# 2020-08-18_Motor_Board.net
KiCad netlist of a schematic drawn in EAGLE
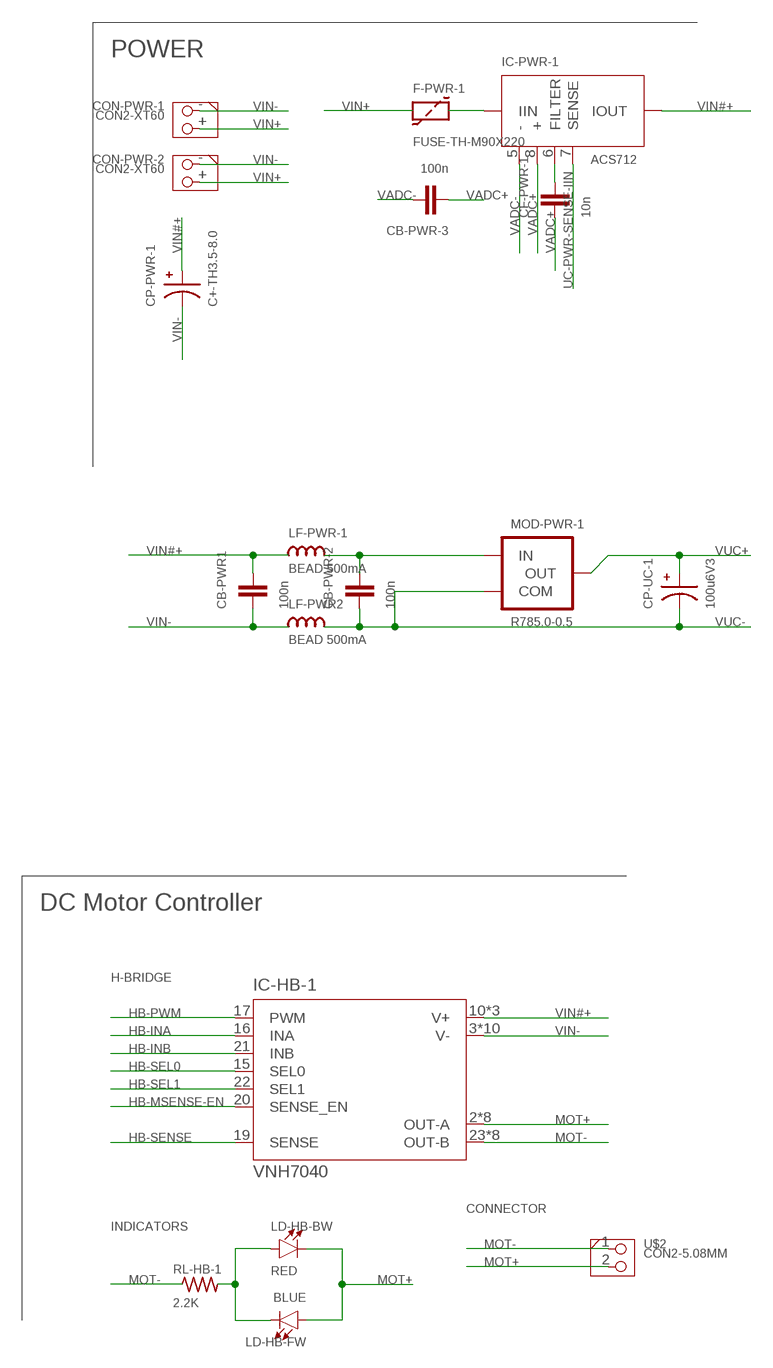
[diagram p0: schematic, sheet 1, part 1 of 2]
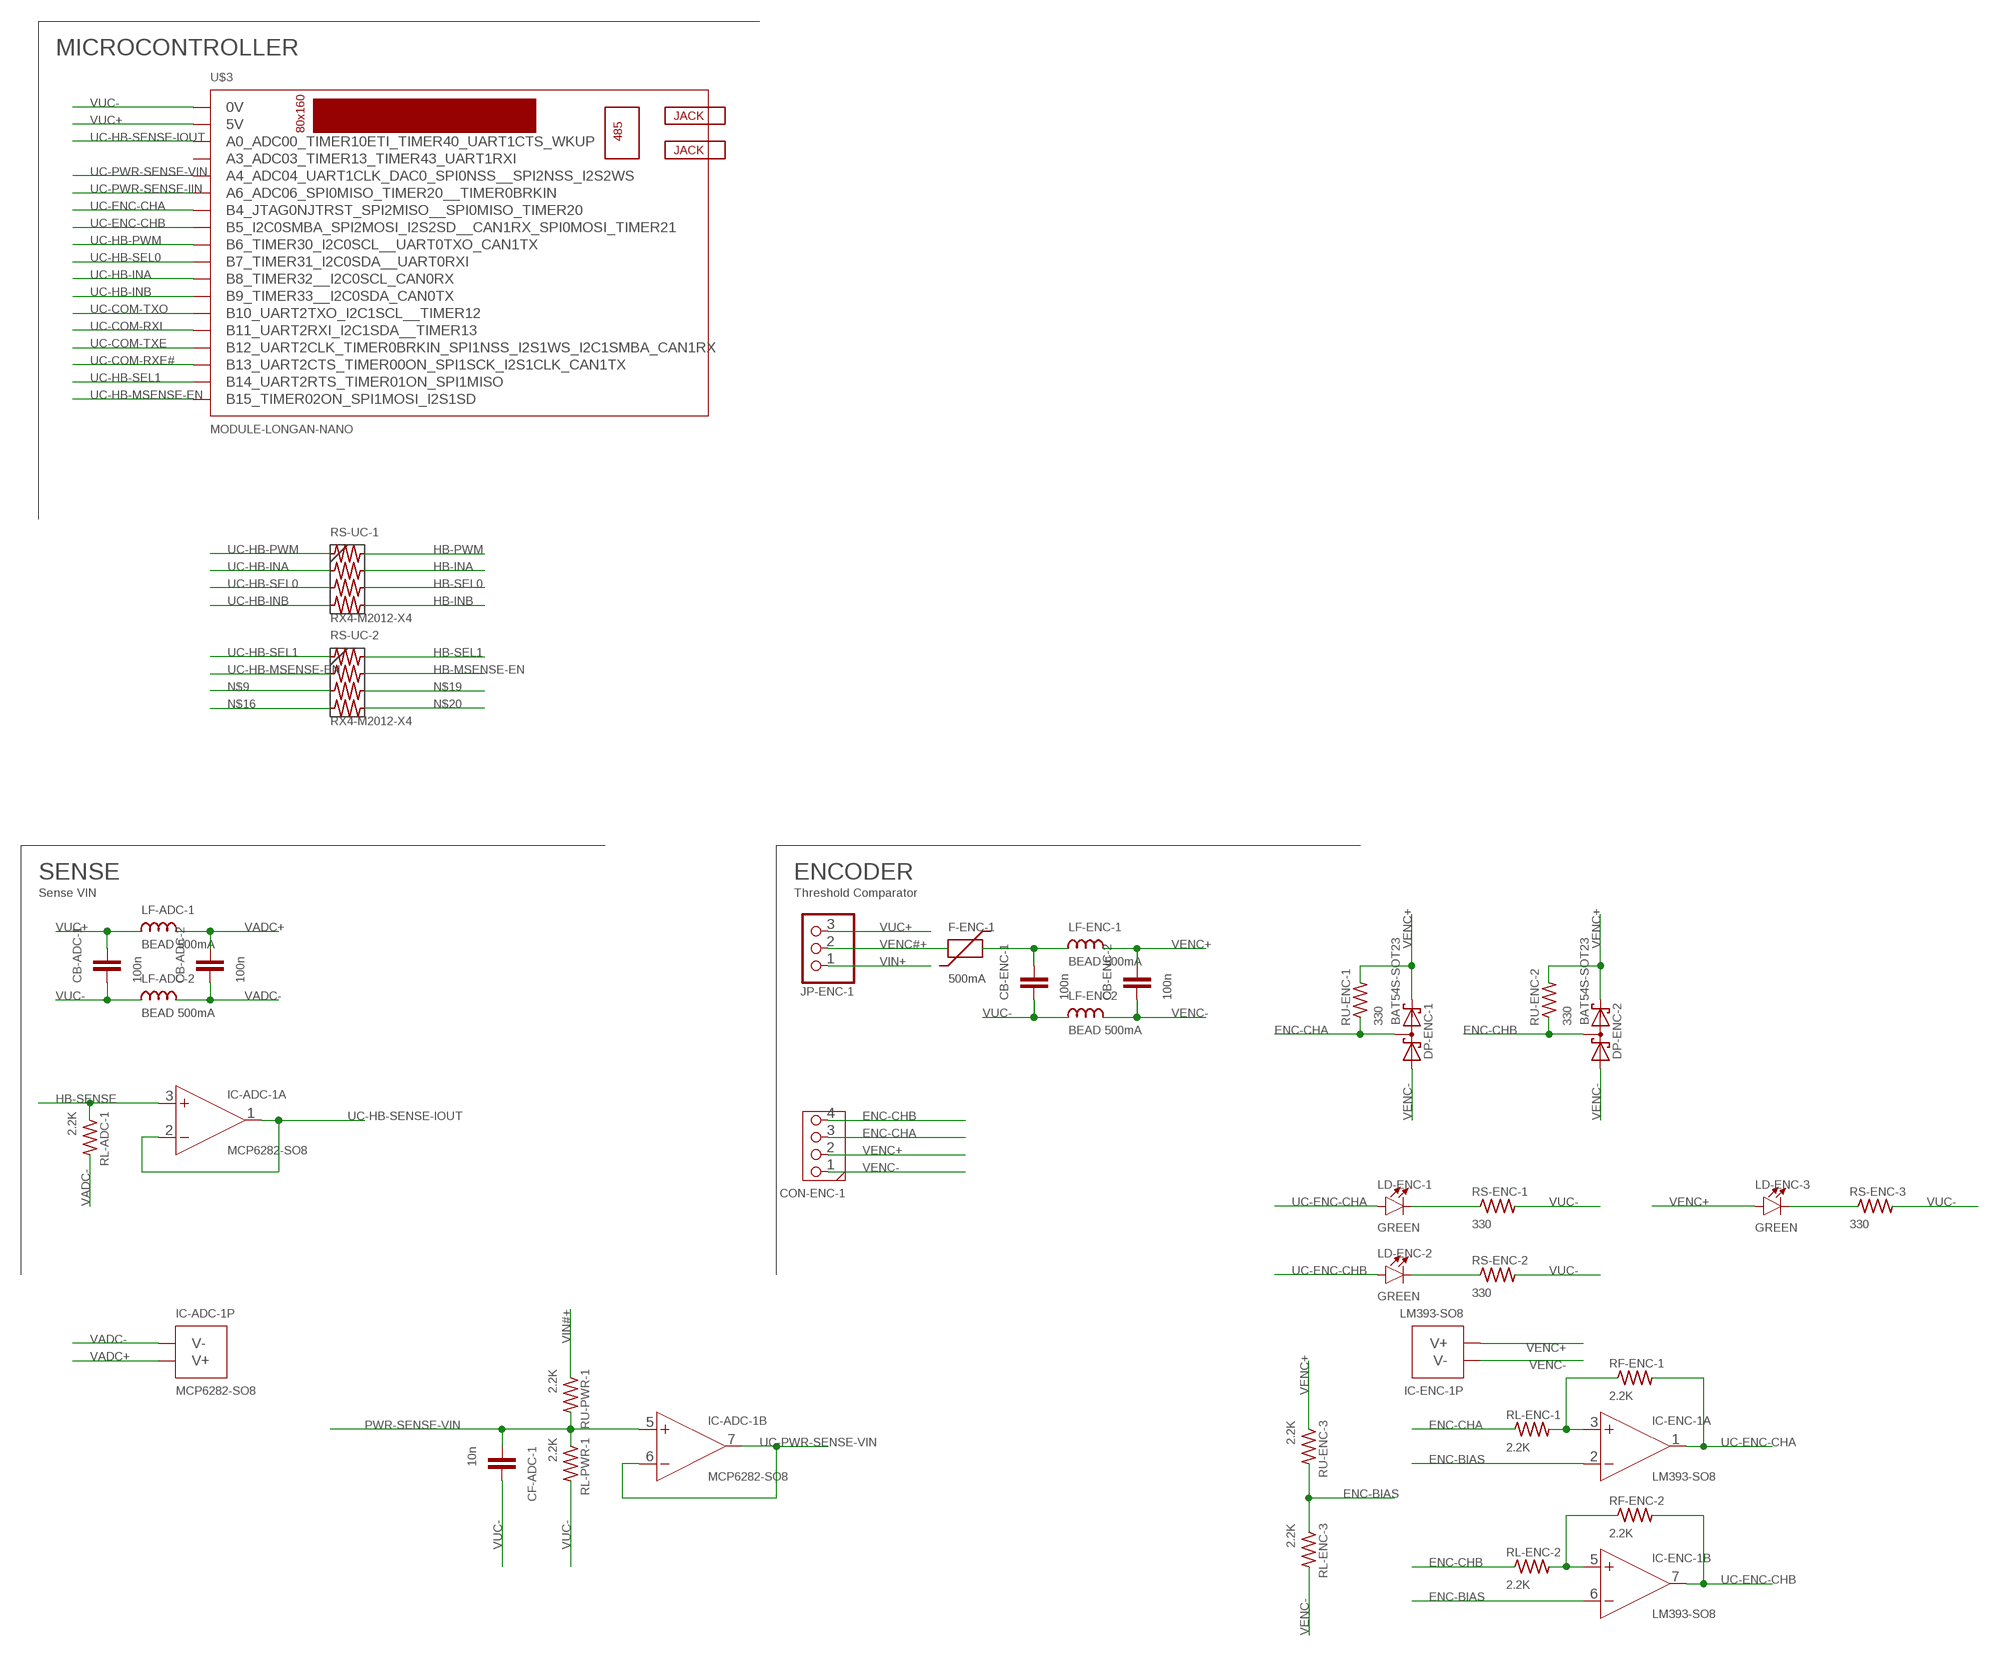
[diagram p1: schematic, sheet 1, part 2 of 2]

(export (version "E")
  (design (tool "Eeschema 10.0.6"))
  (components
    (comp (ref "CB-ADC-1")
      (value "100n")
      (footprint "eagle-import:SMD-M2012")
      (libsource (lib "eagle-import") (part "C-M2012"))
    )
    (comp (ref "CB-ADC-2")
      (value "100n")
      (footprint "eagle-import:SMD-M2012")
      (libsource (lib "eagle-import") (part "C-M2012"))
    )
    (comp (ref "CB-ENC-1")
      (value "100n")
      (footprint "eagle-import:SMD-M2012")
      (libsource (lib "eagle-import") (part "C-M2012"))
    )
    (comp (ref "CB-ENC-2")
      (value "100n")
      (footprint "eagle-import:SMD-M2012")
      (libsource (lib "eagle-import") (part "C-M2012"))
    )
    (comp (ref "CB-PWR-2")
      (value "100n")
      (footprint "eagle-import:SMD-M2012")
      (libsource (lib "eagle-import") (part "C-M2012"))
    )
    (comp (ref "CB-PWR-3")
      (value "100n")
      (footprint "eagle-import:SMD-M2012")
      (libsource (lib "eagle-import") (part "C-M2012"))
    )
    (comp (ref "CB-PWR1")
      (value "100n")
      (footprint "eagle-import:SMD-M2012")
      (libsource (lib "eagle-import") (part "C-M2012"))
    )
    (comp (ref "CF-ADC-1")
      (value "10n")
      (footprint "eagle-import:SMD-M2012")
      (libsource (lib "eagle-import") (part "C-M2012"))
    )
    (comp (ref "CF-PWR-1")
      (value "10n")
      (footprint "eagle-import:SMD-M2012")
      (libsource (lib "eagle-import") (part "C-M2012"))
    )
    (comp (ref "CON-ENC-1")
      (value "CON4")
      (footprint "eagle-import:CON4")
      (libsource (lib "eagle-import") (part "CON4"))
    )
    (comp (ref "CON-PWR-1")
      (value "CON2-XT60")
      (footprint "eagle-import:AMASS_XT60-M")
      (libsource (lib "eagle-import") (part "CON2-XT60"))
    )
    (comp (ref "CON-PWR-2")
      (value "CON2-XT60")
      (footprint "eagle-import:AMASS_XT60-M")
      (libsource (lib "eagle-import") (part "CON2-XT60"))
    )
    (comp (ref "CP-PWR-1")
      (value "C+-TH3.5-8.0")
      (footprint "eagle-import:TH-BARREL-3M5-8M0")
      (libsource (lib "eagle-import") (part "C+-TH3.5-8.0"))
    )
    (comp (ref "CP-UC-1")
      (value "100u6V3")
      (footprint "eagle-import:TH-BARREL-2M54-6M0")
      (libsource (lib "eagle-import") (part "C+-TH2.54-6.0"))
    )
    (comp (ref "DP-ENC-1")
      (value "BAT54S-SOT23")
      (footprint "eagle-import:SOT23")
      (libsource (lib "eagle-import") (part "BAT54S-SOT23"))
    )
    (comp (ref "DP-ENC-2")
      (value "BAT54S-SOT23")
      (footprint "eagle-import:SOT23")
      (libsource (lib "eagle-import") (part "BAT54S-SOT23"))
    )
    (comp (ref "F-ENC-1")
      (value "500mA")
      (footprint "eagle-import:SMD-M2012")
      (libsource (lib "eagle-import") (part "PTC-M2012"))
    )
    (comp (ref "F-PWR-1")
      (value "FUSE-TH-M90X220")
      (footprint "eagle-import:TH-BOX-MM9X22")
      (libsource (lib "eagle-import") (part "FUSE-TH-M90X220"))
    )
    (comp (ref "IC-ADC-1")
      (value "MCP6282-SO8")
      (footprint "eagle-import:SO8")
      (libsource (lib "eagle-import") (part "MCP6282-SO8"))
    )
    (comp (ref "IC-ENC-1")
      (value "LM393-SO8")
      (footprint "eagle-import:SO8")
      (libsource (lib "eagle-import") (part "LM393-SO8"))
    )
    (comp (ref "IC-HB-1")
      (value "VNH7040")
      (footprint "eagle-import:SSO-36-TP")
      (libsource (lib "eagle-import") (part "VNH7040"))
    )
    (comp (ref "IC-PWR-1")
      (value "ACS712")
      (footprint "eagle-import:SO8")
      (libsource (lib "eagle-import") (part "ACS712"))
    )
    (comp (ref "JP-ENC-1")
      (value "PINHD-1X3")
      (footprint "eagle-import:1X03")
      (libsource (lib "eagle-import") (part "PINHD-1X3"))
    )
    (comp (ref "LD-ENC-1")
      (value "GREEN")
      (footprint "eagle-import:SMD-M2012-POL")
      (libsource (lib "eagle-import") (part "LED-M2012"))
    )
    (comp (ref "LD-ENC-2")
      (value "GREEN")
      (footprint "eagle-import:SMD-M2012-POL")
      (libsource (lib "eagle-import") (part "LED-M2012"))
    )
    (comp (ref "LD-ENC-3")
      (value "GREEN")
      (footprint "eagle-import:SMD-M2012-POL")
      (libsource (lib "eagle-import") (part "LED-M2012"))
    )
    (comp (ref "LD-HB-BW")
      (value "RED")
      (footprint "eagle-import:SMD-M2012-POL")
      (libsource (lib "eagle-import") (part "LED-M2012"))
    )
    (comp (ref "LD-HB-FW")
      (value "BLUE")
      (footprint "eagle-import:SMD-M2012-POL")
      (libsource (lib "eagle-import") (part "LED-M2012"))
    )
    (comp (ref "LF-ADC-1")
      (value "BEAD 500mA")
      (footprint "eagle-import:SMD-M2012")
      (libsource (lib "eagle-import") (part "L-M2012"))
    )
    (comp (ref "LF-ADC-2")
      (value "BEAD 500mA")
      (footprint "eagle-import:SMD-M2012")
      (libsource (lib "eagle-import") (part "L-M2012"))
    )
    (comp (ref "LF-ENC-1")
      (value "BEAD 500mA")
      (footprint "eagle-import:SMD-M2012")
      (libsource (lib "eagle-import") (part "L-M2012"))
    )
    (comp (ref "LF-ENC2")
      (value "BEAD 500mA")
      (footprint "eagle-import:SMD-M2012")
      (libsource (lib "eagle-import") (part "L-M2012"))
    )
    (comp (ref "LF-PWR-1")
      (value "BEAD 500mA")
      (footprint "eagle-import:SMD-M2012")
      (libsource (lib "eagle-import") (part "L-M2012"))
    )
    (comp (ref "LF-PWR2")
      (value "BEAD 500mA")
      (footprint "eagle-import:SMD-M2012")
      (libsource (lib "eagle-import") (part "L-M2012"))
    )
    (comp (ref "MOD-PWR-1")
      (value "R785.0-0.5")
      (footprint "eagle-import:CUSTOM_SIP3_PIN")
      (libsource (lib "eagle-import") (part "78XX"))
    )
    (comp (ref "RF-ENC-1")
      (value "2.2K")
      (footprint "eagle-import:SMD-M2012")
      (libsource (lib "eagle-import") (part "R-M2012"))
    )
    (comp (ref "RF-ENC-2")
      (value "2.2K")
      (footprint "eagle-import:SMD-M2012")
      (libsource (lib "eagle-import") (part "R-M2012"))
    )
    (comp (ref "RL-ADC-1")
      (value "2.2K")
      (footprint "eagle-import:SMD-M2012")
      (libsource (lib "eagle-import") (part "R-M2012"))
    )
    (comp (ref "RL-ENC-1")
      (value "2.2K")
      (footprint "eagle-import:SMD-M2012")
      (libsource (lib "eagle-import") (part "R-M2012"))
    )
    (comp (ref "RL-ENC-2")
      (value "2.2K")
      (footprint "eagle-import:SMD-M2012")
      (libsource (lib "eagle-import") (part "R-M2012"))
    )
    (comp (ref "RL-ENC-3")
      (value "2.2K")
      (footprint "eagle-import:SMD-M2012")
      (libsource (lib "eagle-import") (part "R-M2012"))
    )
    (comp (ref "RL-HB-1")
      (value "2.2K")
      (footprint "eagle-import:SMD-M2012")
      (libsource (lib "eagle-import") (part "R-M2012"))
    )
    (comp (ref "RL-PWR-1")
      (value "2.2K")
      (footprint "eagle-import:SMD-M2012")
      (libsource (lib "eagle-import") (part "R-M2012"))
    )
    (comp (ref "RS-ENC-1")
      (value "330")
      (footprint "eagle-import:SMD-M2012")
      (libsource (lib "eagle-import") (part "R-M2012"))
    )
    (comp (ref "RS-ENC-2")
      (value "330")
      (footprint "eagle-import:SMD-M2012")
      (libsource (lib "eagle-import") (part "R-M2012"))
    )
    (comp (ref "RS-ENC-3")
      (value "330")
      (footprint "eagle-import:SMD-M2012")
      (libsource (lib "eagle-import") (part "R-M2012"))
    )
    (comp (ref "RS-UC-1")
      (value "RX4-M2012-X4")
      (footprint "eagle-import:SMD-M2012-X4")
      (libsource (lib "eagle-import") (part "RX4-M2012-X4"))
    )
    (comp (ref "RS-UC-2")
      (value "RX4-M2012-X4")
      (footprint "eagle-import:SMD-M2012-X4")
      (libsource (lib "eagle-import") (part "RX4-M2012-X4"))
    )
    (comp (ref "RU-ENC-1")
      (value "330")
      (footprint "eagle-import:SMD-M2012")
      (libsource (lib "eagle-import") (part "R-M2012"))
    )
    (comp (ref "RU-ENC-2")
      (value "330")
      (footprint "eagle-import:SMD-M2012")
      (libsource (lib "eagle-import") (part "R-M2012"))
    )
    (comp (ref "RU-ENC-3")
      (value "2.2K")
      (footprint "eagle-import:SMD-M2012")
      (libsource (lib "eagle-import") (part "R-M2012"))
    )
    (comp (ref "RU-PWR-1")
      (value "2.2K")
      (footprint "eagle-import:SMD-M2012")
      (libsource (lib "eagle-import") (part "R-M2012"))
    )
    (comp (ref "U$2")
      (value "CON2-5.08MM")
      (footprint "eagle-import:CON2-508")
      (libsource (lib "eagle-import") (part "CON2-5.08MM"))
    )
    (comp (ref "U$3")
      (value "MODULE-LONGAN-NANO")
      (footprint "eagle-import:MODULE-LONGAN-NANO")
      (libsource (lib "eagle-import") (part "MODULE-LONGAN-NANO"))
    )
  )
  (nets
    (net (code "1") (name "/ENC-BIAS") (class "Default")
      (node (ref "IC-ENC-1") (pin "2") (pinfunction "-IN_2") (pintype "input"))
      (node (ref "IC-ENC-1") (pin "6") (pinfunction "-IN_6") (pintype "input"))
      (node (ref "RL-ENC-3") (pin "1") (pinfunction "1_1") (pintype "passive"))
      (node (ref "RU-ENC-3") (pin "2") (pinfunction "2_2") (pintype "passive"))
    )
    (net (code "2") (name "/ENC-CHA") (class "Default")
      (node (ref "CON-ENC-1") (pin "3") (pinfunction "3_3") (pintype "passive"))
      (node (ref "DP-ENC-1") (pin "3") (pinfunction "C1A2_3") (pintype "passive"))
      (node (ref "RL-ENC-1") (pin "1") (pinfunction "1_1") (pintype "passive"))
      (node (ref "RU-ENC-1") (pin "1") (pinfunction "1_1") (pintype "passive"))
    )
    (net (code "3") (name "/ENC-CHB") (class "Default")
      (node (ref "CON-ENC-1") (pin "4") (pinfunction "4_4") (pintype "passive"))
      (node (ref "DP-ENC-2") (pin "3") (pinfunction "C1A2_3") (pintype "passive"))
      (node (ref "RL-ENC-2") (pin "1") (pinfunction "1_1") (pintype "passive"))
      (node (ref "RU-ENC-2") (pin "1") (pinfunction "1_1") (pintype "passive"))
    )
    (net (code "4") (name "/HB-INA") (class "Default")
      (node (ref "IC-HB-1") (pin "16") (pinfunction "INA_16") (pintype "input"))
      (node (ref "RS-UC-1") (pin "2B") (pinfunction "2B_2B") (pintype "bidirectional"))
    )
    (net (code "5") (name "/HB-INB") (class "Default")
      (node (ref "IC-HB-1") (pin "21") (pinfunction "INB_21") (pintype "input"))
      (node (ref "RS-UC-1") (pin "4B") (pinfunction "4B_4B") (pintype "bidirectional"))
    )
    (net (code "6") (name "/HB-MSENSE-EN") (class "Default")
      (node (ref "IC-HB-1") (pin "20") (pinfunction "SENSE_EN_20") (pintype "input"))
      (node (ref "RS-UC-2") (pin "2B") (pinfunction "2B_2B") (pintype "bidirectional"))
    )
    (net (code "7") (name "/HB-PWM") (class "Default")
      (node (ref "IC-HB-1") (pin "17") (pinfunction "PWM_17") (pintype "input"))
      (node (ref "RS-UC-1") (pin "1B") (pinfunction "1B_1B") (pintype "bidirectional"))
    )
    (net (code "8") (name "/HB-SEL0") (class "Default")
      (node (ref "IC-HB-1") (pin "15") (pinfunction "SEL0_15") (pintype "input"))
      (node (ref "RS-UC-1") (pin "3B") (pinfunction "3B_3B") (pintype "bidirectional"))
    )
    (net (code "9") (name "/HB-SEL1") (class "Default")
      (node (ref "IC-HB-1") (pin "22") (pinfunction "SEL1_22") (pintype "input"))
      (node (ref "RS-UC-2") (pin "1B") (pinfunction "1B_1B") (pintype "bidirectional"))
    )
    (net (code "10") (name "/HB-SENSE") (class "Default")
      (node (ref "IC-ADC-1") (pin "3") (pinfunction "+IN_3") (pintype "input"))
      (node (ref "IC-HB-1") (pin "19") (pinfunction "SENSE_19") (pintype "output"))
      (node (ref "RL-ADC-1") (pin "1") (pinfunction "1_1") (pintype "passive"))
    )
    (net (code "11") (name "/MOT+") (class "Default")
      (node (ref "IC-HB-1") (pin "11") (pinfunction "OUT-A_11") (pintype "passive"))
      (node (ref "IC-HB-1") (pin "12") (pinfunction "OUT-A_12") (pintype "passive"))
      (node (ref "IC-HB-1") (pin "13") (pinfunction "OUT-A_13") (pintype "passive"))
      (node (ref "IC-HB-1") (pin "14") (pinfunction "OUT-A_14") (pintype "passive"))
      (node (ref "IC-HB-1") (pin "2") (pinfunction "OUT-A_2") (pintype "passive"))
      (node (ref "IC-HB-1") (pin "8") (pinfunction "OUT-A_8") (pintype "passive"))
      (node (ref "IC-HB-1") (pin "9") (pinfunction "OUT-A_9") (pintype "passive"))
      (node (ref "IC-HB-1") (pin "PAD2") (pinfunction "OUT-A_PAD2") (pintype "passive"))
      (node (ref "LD-HB-BW") (pin "-") (pinfunction "-_-") (pintype "passive"))
      (node (ref "LD-HB-FW") (pin "+") (pinfunction "+_+") (pintype "passive"))
      (node (ref "U$2") (pin "2") (pinfunction "2_2") (pintype "passive"))
    )
    (net (code "12") (name "/MOT-") (class "Default")
      (node (ref "IC-HB-1") (pin "23") (pinfunction "OUT-B_23") (pintype "passive"))
      (node (ref "IC-HB-1") (pin "24") (pinfunction "OUT-B_24") (pintype "passive"))
      (node (ref "IC-HB-1") (pin "25") (pinfunction "OUT-B_25") (pintype "passive"))
      (node (ref "IC-HB-1") (pin "26") (pinfunction "OUT-B_26") (pintype "passive"))
      (node (ref "IC-HB-1") (pin "28") (pinfunction "OUT-B_28") (pintype "passive"))
      (node (ref "IC-HB-1") (pin "29") (pinfunction "OUT-B_29") (pintype "passive"))
      (node (ref "IC-HB-1") (pin "35") (pinfunction "OUT-B_35") (pintype "passive"))
      (node (ref "IC-HB-1") (pin "PAD3") (pinfunction "OUT-B_PAD3") (pintype "passive"))
      (node (ref "RL-HB-1") (pin "1") (pinfunction "1_1") (pintype "passive"))
      (node (ref "U$2") (pin "1") (pinfunction "1_1") (pintype "passive"))
    )
    (net (code "13") (name "/N$9") (class "Default")
      (node (ref "RS-UC-2") (pin "3A") (pinfunction "3A_3A") (pintype "bidirectional"))
    )
    (net (code "14") (name "/N$16") (class "Default")
      (node (ref "RS-UC-2") (pin "4A") (pinfunction "4A_4A") (pintype "bidirectional"))
    )
    (net (code "15") (name "/N$19") (class "Default")
      (node (ref "RS-UC-2") (pin "3B") (pinfunction "3B_3B") (pintype "bidirectional"))
    )
    (net (code "16") (name "/N$20") (class "Default")
      (node (ref "RS-UC-2") (pin "4B") (pinfunction "4B_4B") (pintype "bidirectional"))
    )
    (net (code "17") (name "/PWR-SENSE-VIN") (class "Default")
      (node (ref "CF-ADC-1") (pin "1") (pinfunction "1_1") (pintype "passive"))
      (node (ref "IC-ADC-1") (pin "5") (pinfunction "+IN_5") (pintype "input"))
      (node (ref "RL-PWR-1") (pin "1") (pinfunction "1_1") (pintype "passive"))
      (node (ref "RU-PWR-1") (pin "2") (pinfunction "2_2") (pintype "passive"))
    )
    (net (code "18") (name "/UC-COM-RXE#") (class "Default")
      (node (ref "U$3") (pin "B13") (pinfunction "B13_UART2CTS_TIMER00ON_SPI1SCK_I2S1CLK_CAN1TX_B13") (pintype "bidirectional"))
    )
    (net (code "19") (name "/UC-COM-RXI") (class "Default")
      (node (ref "U$3") (pin "B11") (pinfunction "B11_UART2RXI_I2C1SDA__TIMER13_B11") (pintype "bidirectional"))
    )
    (net (code "20") (name "/UC-COM-TXE") (class "Default")
      (node (ref "U$3") (pin "B12") (pinfunction "B12_UART2CLK_TIMER0BRKIN_SPI1NSS_I2S1WS_I2C1SMBA_CAN1RX_B12") (pintype "bidirectional"))
    )
    (net (code "21") (name "/UC-COM-TXO") (class "Default")
      (node (ref "U$3") (pin "B10") (pinfunction "B10_UART2TXO_I2C1SCL__TIMER12_B10") (pintype "bidirectional"))
    )
    (net (code "22") (name "/UC-ENC-CHA") (class "Default")
      (node (ref "IC-ENC-1") (pin "1") (pinfunction "OUT_1") (pintype "output"))
      (node (ref "LD-ENC-1") (pin "+") (pinfunction "+_+") (pintype "passive"))
      (node (ref "RF-ENC-1") (pin "2") (pinfunction "2_2") (pintype "passive"))
      (node (ref "U$3") (pin "B4") (pinfunction "B4_JTAG0NJTRST_SPI2MISO__SPI0MISO_TIMER20_B4") (pintype "bidirectional"))
    )
    (net (code "23") (name "/UC-ENC-CHB") (class "Default")
      (node (ref "IC-ENC-1") (pin "7") (pinfunction "OUT_7") (pintype "output"))
      (node (ref "LD-ENC-2") (pin "+") (pinfunction "+_+") (pintype "passive"))
      (node (ref "RF-ENC-2") (pin "2") (pinfunction "2_2") (pintype "passive"))
      (node (ref "U$3") (pin "B5") (pinfunction "B5_I2C0SMBA_SPI2MOSI_I2S2SD__CAN1RX_SPI0MOSI_TIMER21_B5") (pintype "bidirectional"))
    )
    (net (code "24") (name "/UC-HB-INA") (class "Default")
      (node (ref "RS-UC-1") (pin "2A") (pinfunction "2A_2A") (pintype "bidirectional"))
      (node (ref "U$3") (pin "B8") (pinfunction "B8_TIMER32__I2C0SCL_CAN0RX_B8") (pintype "bidirectional"))
    )
    (net (code "25") (name "/UC-HB-INB") (class "Default")
      (node (ref "RS-UC-1") (pin "4A") (pinfunction "4A_4A") (pintype "bidirectional"))
      (node (ref "U$3") (pin "B9") (pinfunction "B9_TIMER33__I2C0SDA_CAN0TX_B9") (pintype "bidirectional"))
    )
    (net (code "26") (name "/UC-HB-MSENSE-EN") (class "Default")
      (node (ref "RS-UC-2") (pin "2A") (pinfunction "2A_2A") (pintype "bidirectional"))
      (node (ref "U$3") (pin "B15") (pinfunction "B15_TIMER02ON_SPI1MOSI_I2S1SD_B15") (pintype "bidirectional"))
    )
    (net (code "27") (name "/UC-HB-PWM") (class "Default")
      (node (ref "RS-UC-1") (pin "1A") (pinfunction "1A_1A") (pintype "bidirectional"))
      (node (ref "U$3") (pin "B6") (pinfunction "B6_TIMER30_I2C0SCL__UART0TXO_CAN1TX_B6") (pintype "bidirectional"))
    )
    (net (code "28") (name "/UC-HB-SEL0") (class "Default")
      (node (ref "RS-UC-1") (pin "3A") (pinfunction "3A_3A") (pintype "bidirectional"))
      (node (ref "U$3") (pin "B7") (pinfunction "B7_TIMER31_I2C0SDA__UART0RXI_B7") (pintype "bidirectional"))
    )
    (net (code "29") (name "/UC-HB-SEL1") (class "Default")
      (node (ref "RS-UC-2") (pin "1A") (pinfunction "1A_1A") (pintype "bidirectional"))
      (node (ref "U$3") (pin "B14") (pinfunction "B14_UART2RTS_TIMER01ON_SPI1MISO_B14") (pintype "bidirectional"))
    )
    (net (code "30") (name "/UC-HB-SENSE-IOUT") (class "Default")
      (node (ref "IC-ADC-1") (pin "1") (pinfunction "OUT_1") (pintype "output"))
      (node (ref "IC-ADC-1") (pin "2") (pinfunction "-IN_2") (pintype "input"))
      (node (ref "U$3") (pin "A0") (pinfunction "A0_ADC00_TIMER10ETI_TIMER40_UART1CTS_WKUP_A0") (pintype "bidirectional"))
    )
    (net (code "31") (name "/UC-PWR-SENSE-IIN") (class "Default")
      (node (ref "IC-PWR-1") (pin "7") (pinfunction "SENSE_7") (pintype "output"))
      (node (ref "U$3") (pin "A6") (pinfunction "A6_ADC06_SPI0MISO_TIMER20__TIMER0BRKIN_A6") (pintype "bidirectional"))
    )
    (net (code "32") (name "/UC-PWR-SENSE-VIN") (class "Default")
      (node (ref "IC-ADC-1") (pin "6") (pinfunction "-IN_6") (pintype "input"))
      (node (ref "IC-ADC-1") (pin "7") (pinfunction "OUT_7") (pintype "output"))
      (node (ref "U$3") (pin "A4") (pinfunction "A4_ADC04_UART1CLK_DAC0_SPI0NSS__SPI2NSS_I2S2WS_A4") (pintype "bidirectional"))
    )
    (net (code "33") (name "/VADC+") (class "Default")
      (node (ref "CB-ADC-2") (pin "2") (pinfunction "2_2") (pintype "passive"))
      (node (ref "CB-PWR-3") (pin "1") (pinfunction "1_1") (pintype "passive"))
      (node (ref "CF-PWR-1") (pin "1") (pinfunction "1_1") (pintype "passive"))
      (node (ref "IC-ADC-1") (pin "8") (pinfunction "V+_8") (pintype "power_in"))
      (node (ref "IC-PWR-1") (pin "8") (pinfunction "+_8") (pintype "power_in"))
      (node (ref "LF-ADC-1") (pin "2") (pinfunction "2_2") (pintype "passive"))
    )
    (net (code "34") (name "/VADC-") (class "Default")
      (node (ref "CB-ADC-2") (pin "1") (pinfunction "1_1") (pintype "passive"))
      (node (ref "CB-PWR-3") (pin "2") (pinfunction "2_2") (pintype "passive"))
      (node (ref "IC-ADC-1") (pin "4") (pinfunction "V-_4") (pintype "power_in"))
      (node (ref "IC-PWR-1") (pin "5") (pinfunction "-_5") (pintype "power_in"))
      (node (ref "LF-ADC-2") (pin "2") (pinfunction "2_2") (pintype "passive"))
      (node (ref "RL-ADC-1") (pin "2") (pinfunction "2_2") (pintype "passive"))
    )
    (net (code "35") (name "/VENC#+") (class "Default")
      (node (ref "F-ENC-1") (pin "1") (pinfunction "1_1") (pintype "passive"))
      (node (ref "JP-ENC-1") (pin "2") (pinfunction "2_2") (pintype "passive"))
    )
    (net (code "36") (name "/VENC+") (class "Default")
      (node (ref "CB-ENC-2") (pin "2") (pinfunction "2_2") (pintype "passive"))
      (node (ref "CON-ENC-1") (pin "2") (pinfunction "2_2") (pintype "passive"))
      (node (ref "DP-ENC-1") (pin "2") (pinfunction "C2_2") (pintype "passive"))
      (node (ref "DP-ENC-2") (pin "2") (pinfunction "C2_2") (pintype "passive"))
      (node (ref "IC-ENC-1") (pin "8") (pinfunction "V+_8") (pintype "power_in"))
      (node (ref "LD-ENC-3") (pin "+") (pinfunction "+_+") (pintype "passive"))
      (node (ref "LF-ENC-1") (pin "2") (pinfunction "2_2") (pintype "passive"))
      (node (ref "RU-ENC-1") (pin "2") (pinfunction "2_2") (pintype "passive"))
      (node (ref "RU-ENC-2") (pin "2") (pinfunction "2_2") (pintype "passive"))
      (node (ref "RU-ENC-3") (pin "1") (pinfunction "1_1") (pintype "passive"))
    )
    (net (code "37") (name "/VENC-") (class "Default")
      (node (ref "CB-ENC-2") (pin "1") (pinfunction "1_1") (pintype "passive"))
      (node (ref "CON-ENC-1") (pin "1") (pinfunction "1_1") (pintype "passive"))
      (node (ref "DP-ENC-1") (pin "1") (pinfunction "A1_1") (pintype "passive"))
      (node (ref "DP-ENC-2") (pin "1") (pinfunction "A1_1") (pintype "passive"))
      (node (ref "IC-ENC-1") (pin "4") (pinfunction "V-_4") (pintype "power_in"))
      (node (ref "LF-ENC2") (pin "2") (pinfunction "2_2") (pintype "passive"))
      (node (ref "RL-ENC-3") (pin "2") (pinfunction "2_2") (pintype "passive"))
    )
    (net (code "38") (name "/VIN#+") (class "Default")
      (node (ref "CB-PWR1") (pin "2") (pinfunction "2_2") (pintype "passive"))
      (node (ref "CP-PWR-1") (pin "+") (pinfunction "+_+") (pintype "passive"))
      (node (ref "IC-HB-1") (pin "10") (pinfunction "V+_10") (pintype "passive"))
      (node (ref "IC-HB-1") (pin "27") (pinfunction "V+_27") (pintype "passive"))
      (node (ref "IC-HB-1") (pin "PAD1") (pinfunction "V+_PAD1") (pintype "passive"))
      (node (ref "IC-PWR-1") (pin "3") (pinfunction "IOUT_3") (pintype "power_in"))
      (node (ref "IC-PWR-1") (pin "4") (pinfunction "IOUT_4") (pintype "power_in"))
      (node (ref "LF-PWR-1") (pin "1") (pinfunction "1_1") (pintype "passive"))
      (node (ref "RU-PWR-1") (pin "1") (pinfunction "1_1") (pintype "passive"))
    )
    (net (code "39") (name "/VIN+") (class "Default")
      (node (ref "CON-PWR-1") (pin "+") (pinfunction "2_+") (pintype "passive"))
      (node (ref "CON-PWR-2") (pin "+") (pinfunction "2_+") (pintype "passive"))
      (node (ref "F-PWR-1") (pin "1") (pinfunction "1_1") (pintype "passive"))
      (node (ref "JP-ENC-1") (pin "1") (pinfunction "1_1") (pintype "passive"))
    )
    (net (code "40") (name "/VIN-") (class "Default")
      (node (ref "CB-PWR1") (pin "1") (pinfunction "1_1") (pintype "passive"))
      (node (ref "CON-PWR-1") (pin "-") (pinfunction "1_-") (pintype "passive"))
      (node (ref "CON-PWR-2") (pin "-") (pinfunction "1_-") (pintype "passive"))
      (node (ref "CP-PWR-1") (pin "-") (pinfunction "-_-") (pintype "passive"))
      (node (ref "IC-HB-1") (pin "3") (pinfunction "V-_3") (pintype "passive"))
      (node (ref "IC-HB-1") (pin "30") (pinfunction "V-_30") (pintype "passive"))
      (node (ref "IC-HB-1") (pin "31") (pinfunction "V-_31") (pintype "passive"))
      (node (ref "IC-HB-1") (pin "32") (pinfunction "V-_32") (pintype "passive"))
      (node (ref "IC-HB-1") (pin "33") (pinfunction "V-_33") (pintype "passive"))
      (node (ref "IC-HB-1") (pin "34") (pinfunction "V-_34") (pintype "passive"))
      (node (ref "IC-HB-1") (pin "4") (pinfunction "V-_4") (pintype "passive"))
      (node (ref "IC-HB-1") (pin "5") (pinfunction "V-_5") (pintype "passive"))
      (node (ref "IC-HB-1") (pin "6") (pinfunction "V-_6") (pintype "passive"))
      (node (ref "IC-HB-1") (pin "7") (pinfunction "V-_7") (pintype "passive"))
      (node (ref "LF-PWR2") (pin "1") (pinfunction "1_1") (pintype "passive"))
    )
    (net (code "41") (name "/VUC+") (class "Default")
      (node (ref "CB-ADC-1") (pin "2") (pinfunction "2_2") (pintype "passive"))
      (node (ref "CP-UC-1") (pin "+") (pinfunction "+_+") (pintype "passive"))
      (node (ref "JP-ENC-1") (pin "3") (pinfunction "3_3") (pintype "passive"))
      (node (ref "LF-ADC-1") (pin "1") (pinfunction "1_1") (pintype "passive"))
      (node (ref "MOD-PWR-1") (pin "OUT") (pinfunction "OUT_OUT") (pintype "passive"))
      (node (ref "U$3") (pin "5V") (pinfunction "5V_5V") (pintype "passive"))
    )
    (net (code "42") (name "/VUC-") (class "Default")
      (node (ref "CB-ADC-1") (pin "1") (pinfunction "1_1") (pintype "passive"))
      (node (ref "CB-ENC-1") (pin "1") (pinfunction "1_1") (pintype "passive"))
      (node (ref "CB-PWR-2") (pin "1") (pinfunction "1_1") (pintype "passive"))
      (node (ref "CF-ADC-1") (pin "2") (pinfunction "2_2") (pintype "passive"))
      (node (ref "CP-UC-1") (pin "-") (pinfunction "-_-") (pintype "passive"))
      (node (ref "LF-ADC-2") (pin "1") (pinfunction "1_1") (pintype "passive"))
      (node (ref "LF-ENC2") (pin "1") (pinfunction "1_1") (pintype "passive"))
      (node (ref "LF-PWR2") (pin "2") (pinfunction "2_2") (pintype "passive"))
      (node (ref "MOD-PWR-1") (pin "COM") (pinfunction "COM_COM") (pintype "input"))
      (node (ref "RL-PWR-1") (pin "2") (pinfunction "2_2") (pintype "passive"))
      (node (ref "RS-ENC-1") (pin "2") (pinfunction "2_2") (pintype "passive"))
      (node (ref "RS-ENC-2") (pin "2") (pinfunction "2_2") (pintype "passive"))
      (node (ref "RS-ENC-3") (pin "2") (pinfunction "2_2") (pintype "passive"))
      (node (ref "U$3") (pin "0V") (pinfunction "0V_0V") (pintype "passive"))
    )
    (net (code "43") (name "Net-(CB-ENC-1-Pad2)") (class "Default")
      (node (ref "CB-ENC-1") (pin "2") (pinfunction "2_2") (pintype "passive"))
      (node (ref "F-ENC-1") (pin "2") (pinfunction "2_2") (pintype "passive"))
      (node (ref "LF-ENC-1") (pin "1") (pinfunction "1_1") (pintype "passive"))
    )
    (net (code "44") (name "Net-(F-PWR-1-Pad2)") (class "Default")
      (node (ref "F-PWR-1") (pin "2") (pinfunction "2_2") (pintype "passive"))
      (node (ref "IC-PWR-1") (pin "1") (pinfunction "IIN_1") (pintype "power_in"))
      (node (ref "IC-PWR-1") (pin "2") (pinfunction "IIN_2") (pintype "power_in"))
    )
    (net (code "45") (name "Net-(IC-ENC-1A-+IN)") (class "Default")
      (node (ref "IC-ENC-1") (pin "3") (pinfunction "+IN_3") (pintype "input"))
      (node (ref "RF-ENC-1") (pin "1") (pinfunction "1_1") (pintype "passive"))
      (node (ref "RL-ENC-1") (pin "2") (pinfunction "2_2") (pintype "passive"))
    )
    (net (code "46") (name "Net-(IC-ENC-1B-+IN)") (class "Default")
      (node (ref "IC-ENC-1") (pin "5") (pinfunction "+IN_5") (pintype "input"))
      (node (ref "RF-ENC-2") (pin "1") (pinfunction "1_1") (pintype "passive"))
      (node (ref "RL-ENC-2") (pin "2") (pinfunction "2_2") (pintype "passive"))
    )
    (net (code "47") (name "Net-(IC-PWR-1-FILTER)") (class "Default")
      (node (ref "CF-PWR-1") (pin "2") (pinfunction "2_2") (pintype "passive"))
      (node (ref "IC-PWR-1") (pin "6") (pinfunction "FILTER_6") (pintype "passive"))
    )
    (net (code "48") (name "Net-(LD-ENC-1-Pad-)") (class "Default")
      (node (ref "LD-ENC-1") (pin "-") (pinfunction "-_-") (pintype "passive"))
      (node (ref "RS-ENC-1") (pin "1") (pinfunction "1_1") (pintype "passive"))
    )
    (net (code "49") (name "Net-(LD-ENC-2-Pad-)") (class "Default")
      (node (ref "LD-ENC-2") (pin "-") (pinfunction "-_-") (pintype "passive"))
      (node (ref "RS-ENC-2") (pin "1") (pinfunction "1_1") (pintype "passive"))
    )
    (net (code "50") (name "Net-(LD-ENC-3-Pad-)") (class "Default")
      (node (ref "LD-ENC-3") (pin "-") (pinfunction "-_-") (pintype "passive"))
      (node (ref "RS-ENC-3") (pin "1") (pinfunction "1_1") (pintype "passive"))
    )
    (net (code "51") (name "Net-(LD-HB-BW-Pad+)") (class "Default")
      (node (ref "LD-HB-BW") (pin "+") (pinfunction "+_+") (pintype "passive"))
      (node (ref "LD-HB-FW") (pin "-") (pinfunction "-_-") (pintype "passive"))
      (node (ref "RL-HB-1") (pin "2") (pinfunction "2_2") (pintype "passive"))
    )
    (net (code "52") (name "Net-(MOD-PWR-1-IN)") (class "Default")
      (node (ref "CB-PWR-2") (pin "2") (pinfunction "2_2") (pintype "passive"))
      (node (ref "LF-PWR-1") (pin "2") (pinfunction "2_2") (pintype "passive"))
      (node (ref "MOD-PWR-1") (pin "VIN") (pinfunction "IN_VIN") (pintype "input"))
    )
    (net (code "53") (name "unconnected-(U$3-A3_ADC03_TIMER13_TIMER43_UART1RXI-PadA3)") (class "Default")
      (node (ref "U$3") (pin "A3") (pinfunction "A3_ADC03_TIMER13_TIMER43_UART1RXI_A3") (pintype "bidirectional"))
    )
  )
)
